# HW4.net
KiCad netlist of a schematic drawn in EAGLE
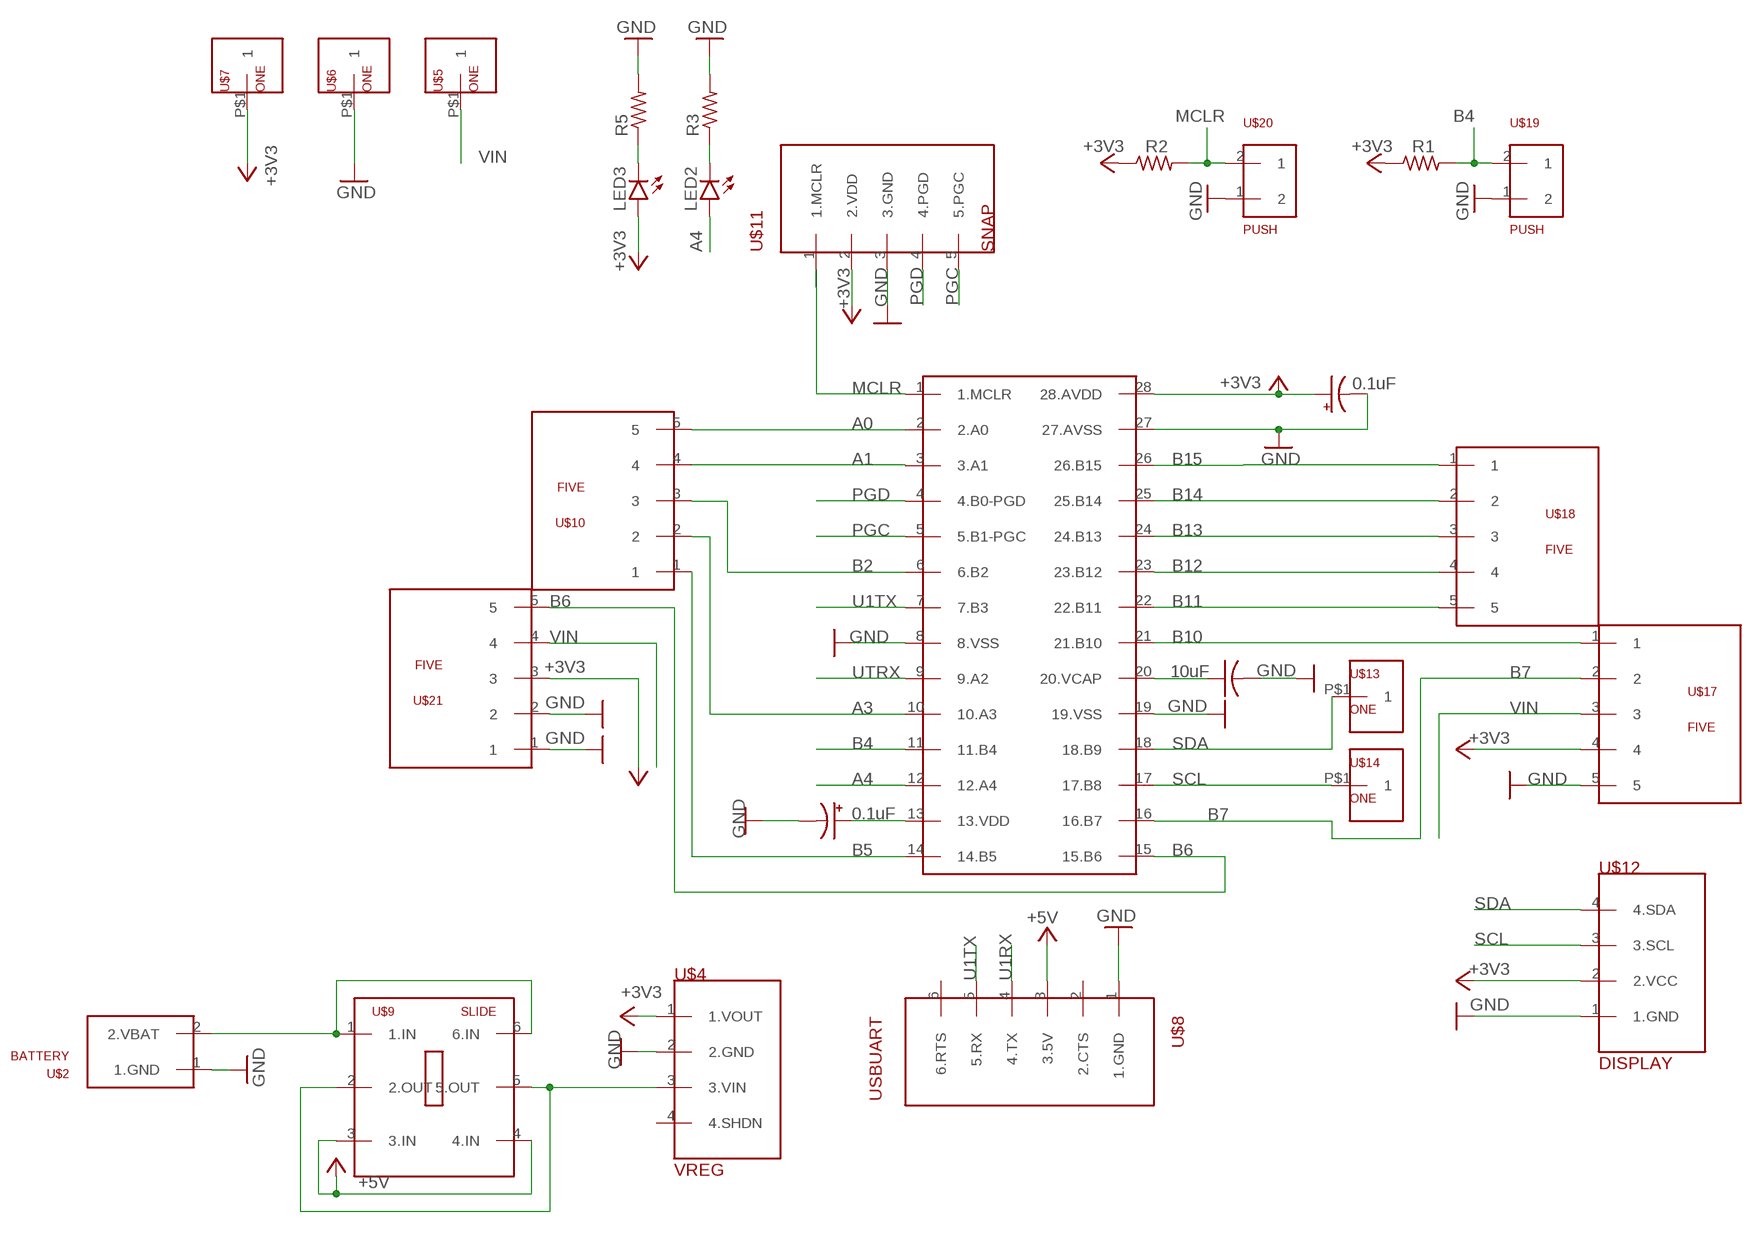
[diagram p0: schematic, sheet 1]

(export (version "E")
  (design (tool "Eeschema 10.0.6"))
  (components
    (comp (ref "C1")
      (value "10uF")
      (footprint "eagle-import:C025-030X050")
      (libsource (lib "eagle-import") (part "C-US025-030X050"))
    )
    (comp (ref "C2")
      (value "0.1uF")
      (footprint "eagle-import:B45181B")
      (libsource (lib "eagle-import") (part "CPOL-USB45181B"))
    )
    (comp (ref "C3")
      (value "0.1uF")
      (footprint "eagle-import:B45181B")
      (libsource (lib "eagle-import") (part "CPOL-USB45181B"))
    )
    (comp (ref "LED2")
      (value "LED3MM")
      (footprint "eagle-import:LED3MM")
      (libsource (lib "eagle-import") (part "LED3MM"))
    )
    (comp (ref "LED3")
      (value "LED3MM")
      (footprint "eagle-import:LED3MM")
      (libsource (lib "eagle-import") (part "LED3MM"))
    )
    (comp (ref "R1")
      (value "R-US_0207/7")
      (footprint "eagle-import:0207_7")
      (libsource (lib "eagle-import") (part "R-US_0207/7"))
    )
    (comp (ref "R2")
      (value "R-US_0207/7")
      (footprint "eagle-import:0207_7")
      (libsource (lib "eagle-import") (part "R-US_0207/7"))
    )
    (comp (ref "R3")
      (value "R-US_0207/7")
      (footprint "eagle-import:0207_7")
      (libsource (lib "eagle-import") (part "R-US_0207/7"))
    )
    (comp (ref "R5")
      (value "R-US_0207/7")
      (footprint "eagle-import:0207_7")
      (libsource (lib "eagle-import") (part "R-US_0207/7"))
    )
    (comp (ref "U$1")
      (value "PIC32MX170F256B")
      (footprint "eagle-import:DIL28-3")
      (libsource (lib "eagle-import") (part "PIC32MX170F256B"))
    )
    (comp (ref "U$2")
      (value "BATTERY")
      (footprint "eagle-import:BATTERY")
      (libsource (lib "eagle-import") (part "BATTERY"))
    )
    (comp (ref "U$4")
      (value "VREG")
      (footprint "eagle-import:VREG")
      (libsource (lib "eagle-import") (part "VREG"))
    )
    (comp (ref "U$5")
      (value "ONE")
      (footprint "eagle-import:ONE")
      (libsource (lib "eagle-import") (part "ONE"))
    )
    (comp (ref "U$6")
      (value "ONE")
      (footprint "eagle-import:ONE")
      (libsource (lib "eagle-import") (part "ONE"))
    )
    (comp (ref "U$7")
      (value "ONE")
      (footprint "eagle-import:ONE")
      (libsource (lib "eagle-import") (part "ONE"))
    )
    (comp (ref "U$8")
      (value "USBUART")
      (footprint "eagle-import:USBUART")
      (libsource (lib "eagle-import") (part "USBUART"))
    )
    (comp (ref "U$9")
      (value "SLIDE")
      (footprint "eagle-import:SLIDE")
      (libsource (lib "eagle-import") (part "SLIDE"))
    )
    (comp (ref "U$10")
      (value "FIVE")
      (footprint "eagle-import:FIVE")
      (libsource (lib "eagle-import") (part "FIVE"))
    )
    (comp (ref "U$11")
      (value "SNAP")
      (footprint "eagle-import:SNAP")
      (libsource (lib "eagle-import") (part "SNAP"))
    )
    (comp (ref "U$12")
      (value "DISPLAY")
      (footprint "eagle-import:DISPLAY")
      (libsource (lib "eagle-import") (part "DISPLAY"))
    )
    (comp (ref "U$13")
      (value "ONE")
      (footprint "eagle-import:ONE")
      (libsource (lib "eagle-import") (part "ONE"))
    )
    (comp (ref "U$14")
      (value "ONE")
      (footprint "eagle-import:ONE")
      (libsource (lib "eagle-import") (part "ONE"))
    )
    (comp (ref "U$17")
      (value "FIVE")
      (footprint "eagle-import:FIVE")
      (libsource (lib "eagle-import") (part "FIVE"))
    )
    (comp (ref "U$18")
      (value "FIVE")
      (footprint "eagle-import:FIVE")
      (libsource (lib "eagle-import") (part "FIVE"))
    )
    (comp (ref "U$19")
      (value "PUSH")
      (footprint "eagle-import:PUSH")
      (libsource (lib "eagle-import") (part "PUSH"))
    )
    (comp (ref "U$20")
      (value "PUSH")
      (footprint "eagle-import:PUSH")
      (libsource (lib "eagle-import") (part "PUSH"))
    )
    (comp (ref "U$21")
      (value "FIVE")
      (footprint "eagle-import:FIVE")
      (libsource (lib "eagle-import") (part "FIVE"))
    )
  )
  (nets
    (net (code "1") (name "+3V3") (class "Default")
      (node (ref "C3") (pin "+") (pinfunction "+_+") (pintype "passive"))
      (node (ref "LED3") (pin "A") (pinfunction "A_A") (pintype "passive"))
      (node (ref "R1") (pin "1") (pinfunction "1_1") (pintype "passive"))
      (node (ref "R2") (pin "1") (pinfunction "1_1") (pintype "passive"))
      (node (ref "U$1") (pin "28") (pinfunction "28.AVDD_28") (pintype "bidirectional"))
      (node (ref "U$11") (pin "2") (pinfunction "2.VDD_2") (pintype "bidirectional"))
      (node (ref "U$12") (pin "2") (pinfunction "2.VCC_2") (pintype "bidirectional"))
      (node (ref "U$17") (pin "4") (pinfunction "4_4") (pintype "bidirectional"))
      (node (ref "U$21") (pin "3") (pinfunction "3_3") (pintype "bidirectional"))
      (node (ref "U$4") (pin "1") (pinfunction "1.VOUT_1") (pintype "bidirectional"))
      (node (ref "U$7") (pin "P$1") (pinfunction "1_P$1") (pintype "bidirectional"))
    )
    (net (code "2") (name "+5V") (class "Default")
      (node (ref "U$8") (pin "3") (pinfunction "3.5V_3") (pintype "bidirectional"))
      (node (ref "U$9") (pin "3") (pinfunction "3.IN_3") (pintype "bidirectional"))
      (node (ref "U$9") (pin "4") (pinfunction "4.IN_4") (pintype "bidirectional"))
    )
    (net (code "3") (name "/A0") (class "Default")
      (node (ref "U$1") (pin "2") (pinfunction "2.A0_2") (pintype "bidirectional"))
      (node (ref "U$10") (pin "5") (pinfunction "5_5") (pintype "bidirectional"))
    )
    (net (code "4") (name "/A1") (class "Default")
      (node (ref "U$1") (pin "3") (pinfunction "3.A1_3") (pintype "bidirectional"))
      (node (ref "U$10") (pin "4") (pinfunction "4_4") (pintype "bidirectional"))
    )
    (net (code "5") (name "/A3") (class "Default")
      (node (ref "U$1") (pin "10") (pinfunction "10.A3_10") (pintype "bidirectional"))
      (node (ref "U$10") (pin "2") (pinfunction "2_2") (pintype "bidirectional"))
    )
    (net (code "6") (name "/A4") (class "Default")
      (node (ref "LED2") (pin "A") (pinfunction "A_A") (pintype "passive"))
      (node (ref "U$1") (pin "12") (pinfunction "12.A4_12") (pintype "bidirectional"))
    )
    (net (code "7") (name "/B2") (class "Default")
      (node (ref "U$1") (pin "6") (pinfunction "6.B2_6") (pintype "bidirectional"))
      (node (ref "U$10") (pin "3") (pinfunction "3_3") (pintype "bidirectional"))
    )
    (net (code "8") (name "/B4") (class "Default")
      (node (ref "R1") (pin "2") (pinfunction "2_2") (pintype "passive"))
      (node (ref "U$1") (pin "11") (pinfunction "11.B4_11") (pintype "bidirectional"))
      (node (ref "U$19") (pin "2") (pinfunction "1_2") (pintype "bidirectional"))
    )
    (net (code "9") (name "/B5") (class "Default")
      (node (ref "U$1") (pin "14") (pinfunction "14.B5_14") (pintype "bidirectional"))
      (node (ref "U$10") (pin "1") (pinfunction "1_1") (pintype "bidirectional"))
    )
    (net (code "10") (name "/B6") (class "Default")
      (node (ref "U$1") (pin "15") (pinfunction "15.B6_15") (pintype "bidirectional"))
      (node (ref "U$21") (pin "5") (pinfunction "5_5") (pintype "bidirectional"))
    )
    (net (code "11") (name "/B7") (class "Default")
      (node (ref "U$1") (pin "16") (pinfunction "16.B7_16") (pintype "bidirectional"))
      (node (ref "U$17") (pin "2") (pinfunction "2_2") (pintype "bidirectional"))
    )
    (net (code "12") (name "/B10") (class "Default")
      (node (ref "U$1") (pin "21") (pinfunction "21.B10_21") (pintype "bidirectional"))
      (node (ref "U$17") (pin "1") (pinfunction "1_1") (pintype "bidirectional"))
    )
    (net (code "13") (name "/B11") (class "Default")
      (node (ref "U$1") (pin "22") (pinfunction "22.B11_22") (pintype "bidirectional"))
      (node (ref "U$18") (pin "5") (pinfunction "5_5") (pintype "bidirectional"))
    )
    (net (code "14") (name "/B12") (class "Default")
      (node (ref "U$1") (pin "23") (pinfunction "23.B12_23") (pintype "bidirectional"))
      (node (ref "U$18") (pin "4") (pinfunction "4_4") (pintype "bidirectional"))
    )
    (net (code "15") (name "/B13") (class "Default")
      (node (ref "U$1") (pin "24") (pinfunction "24.B13_24") (pintype "bidirectional"))
      (node (ref "U$18") (pin "3") (pinfunction "3_3") (pintype "bidirectional"))
    )
    (net (code "16") (name "/B14") (class "Default")
      (node (ref "U$1") (pin "25") (pinfunction "25.B14_25") (pintype "bidirectional"))
      (node (ref "U$18") (pin "2") (pinfunction "2_2") (pintype "bidirectional"))
    )
    (net (code "17") (name "/B15") (class "Default")
      (node (ref "U$1") (pin "26") (pinfunction "26.B15_26") (pintype "bidirectional"))
      (node (ref "U$18") (pin "1") (pinfunction "1_1") (pintype "bidirectional"))
    )
    (net (code "18") (name "/MCLR") (class "Default")
      (node (ref "R2") (pin "2") (pinfunction "2_2") (pintype "passive"))
      (node (ref "U$1") (pin "1") (pinfunction "1.MCLR_1") (pintype "bidirectional"))
      (node (ref "U$11") (pin "1") (pinfunction "1.MCLR_1") (pintype "bidirectional"))
      (node (ref "U$20") (pin "2") (pinfunction "1_2") (pintype "bidirectional"))
    )
    (net (code "19") (name "/PGC") (class "Default")
      (node (ref "U$1") (pin "5") (pinfunction "5.B1-PGC_5") (pintype "bidirectional"))
      (node (ref "U$11") (pin "5") (pinfunction "5.PGC_5") (pintype "bidirectional"))
    )
    (net (code "20") (name "/PGD") (class "Default")
      (node (ref "U$1") (pin "4") (pinfunction "4.B0-PGD_4") (pintype "bidirectional"))
      (node (ref "U$11") (pin "4") (pinfunction "4.PGD_4") (pintype "bidirectional"))
    )
    (net (code "21") (name "/SCL") (class "Default")
      (node (ref "U$1") (pin "17") (pinfunction "17.B8_17") (pintype "bidirectional"))
      (node (ref "U$12") (pin "3") (pinfunction "3.SCL_3") (pintype "bidirectional"))
      (node (ref "U$14") (pin "P$1") (pinfunction "1_P$1") (pintype "bidirectional"))
    )
    (net (code "22") (name "/SDA") (class "Default")
      (node (ref "U$1") (pin "18") (pinfunction "18.B9_18") (pintype "bidirectional"))
      (node (ref "U$12") (pin "4") (pinfunction "4.SDA_4") (pintype "bidirectional"))
      (node (ref "U$13") (pin "P$1") (pinfunction "1_P$1") (pintype "bidirectional"))
    )
    (net (code "23") (name "/U1RX") (class "Default")
      (node (ref "U$8") (pin "4") (pinfunction "4.TX_4") (pintype "bidirectional"))
    )
    (net (code "24") (name "/U1TX") (class "Default")
      (node (ref "U$1") (pin "7") (pinfunction "7.B3_7") (pintype "bidirectional"))
      (node (ref "U$8") (pin "5") (pinfunction "5.RX_5") (pintype "bidirectional"))
    )
    (net (code "25") (name "/UTRX") (class "Default")
      (node (ref "U$1") (pin "9") (pinfunction "9.A2_9") (pintype "bidirectional"))
    )
    (net (code "26") (name "/VIN") (class "Default")
      (node (ref "U$17") (pin "3") (pinfunction "3_3") (pintype "bidirectional"))
      (node (ref "U$21") (pin "4") (pinfunction "4_4") (pintype "bidirectional"))
      (node (ref "U$5") (pin "P$1") (pinfunction "1_P$1") (pintype "bidirectional"))
    )
    (net (code "27") (name "GND") (class "Default")
      (node (ref "C1") (pin "2") (pinfunction "2_2") (pintype "passive"))
      (node (ref "C2") (pin "-") (pinfunction "-_-") (pintype "passive"))
      (node (ref "C3") (pin "-") (pinfunction "-_-") (pintype "passive"))
      (node (ref "R3") (pin "2") (pinfunction "2_2") (pintype "passive"))
      (node (ref "R5") (pin "2") (pinfunction "2_2") (pintype "passive"))
      (node (ref "U$1") (pin "19") (pinfunction "19.VSS_19") (pintype "bidirectional"))
      (node (ref "U$1") (pin "27") (pinfunction "27.AVSS_27") (pintype "bidirectional"))
      (node (ref "U$1") (pin "8") (pinfunction "8.VSS_8") (pintype "bidirectional"))
      (node (ref "U$11") (pin "3") (pinfunction "3.GND_3") (pintype "bidirectional"))
      (node (ref "U$12") (pin "1") (pinfunction "1.GND_1") (pintype "bidirectional"))
      (node (ref "U$17") (pin "5") (pinfunction "5_5") (pintype "bidirectional"))
      (node (ref "U$19") (pin "1") (pinfunction "2_1") (pintype "bidirectional"))
      (node (ref "U$2") (pin "1") (pinfunction "1.GND_1") (pintype "bidirectional"))
      (node (ref "U$20") (pin "1") (pinfunction "2_1") (pintype "bidirectional"))
      (node (ref "U$21") (pin "1") (pinfunction "1_1") (pintype "bidirectional"))
      (node (ref "U$21") (pin "2") (pinfunction "2_2") (pintype "bidirectional"))
      (node (ref "U$4") (pin "2") (pinfunction "2.GND_2") (pintype "bidirectional"))
      (node (ref "U$6") (pin "P$1") (pinfunction "1_P$1") (pintype "bidirectional"))
      (node (ref "U$8") (pin "1") (pinfunction "1.GND_1") (pintype "bidirectional"))
    )
    (net (code "28") (name "Net-(LED2-C)") (class "Default")
      (node (ref "LED2") (pin "K") (pinfunction "C_K") (pintype "passive"))
      (node (ref "R3") (pin "1") (pinfunction "1_1") (pintype "passive"))
    )
    (net (code "29") (name "Net-(LED3-C)") (class "Default")
      (node (ref "LED3") (pin "K") (pinfunction "C_K") (pintype "passive"))
      (node (ref "R5") (pin "1") (pinfunction "1_1") (pintype "passive"))
    )
    (net (code "30") (name "Net-(U$1-13.VDD)") (class "Default")
      (node (ref "C2") (pin "+") (pinfunction "+_+") (pintype "passive"))
      (node (ref "U$1") (pin "13") (pinfunction "13.VDD_13") (pintype "bidirectional"))
    )
    (net (code "31") (name "Net-(U$1-20.VCAP)") (class "Default")
      (node (ref "C1") (pin "1") (pinfunction "1_1") (pintype "passive"))
      (node (ref "U$1") (pin "20") (pinfunction "20.VCAP_20") (pintype "bidirectional"))
    )
    (net (code "32") (name "Net-(U$2-2.VBAT)") (class "Default")
      (node (ref "U$2") (pin "2") (pinfunction "2.VBAT_2") (pintype "bidirectional"))
      (node (ref "U$9") (pin "1") (pinfunction "1.IN_1") (pintype "bidirectional"))
      (node (ref "U$9") (pin "6") (pinfunction "6.IN_6") (pintype "bidirectional"))
    )
    (net (code "33") (name "Net-(U$4-3.VIN)") (class "Default")
      (node (ref "U$4") (pin "3") (pinfunction "3.VIN_3") (pintype "bidirectional"))
      (node (ref "U$9") (pin "2") (pinfunction "2.OUT_2") (pintype "bidirectional"))
      (node (ref "U$9") (pin "5") (pinfunction "5.OUT_5") (pintype "bidirectional"))
    )
    (net (code "34") (name "unconnected-(U$4-4.SHDN-Pad4)") (class "Default")
      (node (ref "U$4") (pin "4") (pinfunction "4.SHDN_4") (pintype "bidirectional"))
    )
    (net (code "35") (name "unconnected-(U$8-2.CTS-Pad2)") (class "Default")
      (node (ref "U$8") (pin "2") (pinfunction "2.CTS_2") (pintype "bidirectional"))
    )
    (net (code "36") (name "unconnected-(U$8-6.RTS-Pad6)") (class "Default")
      (node (ref "U$8") (pin "6") (pinfunction "6.RTS_6") (pintype "bidirectional"))
    )
  )
)
